# H1BR7.net
KiCad netlist of a schematic drawn in EAGLE
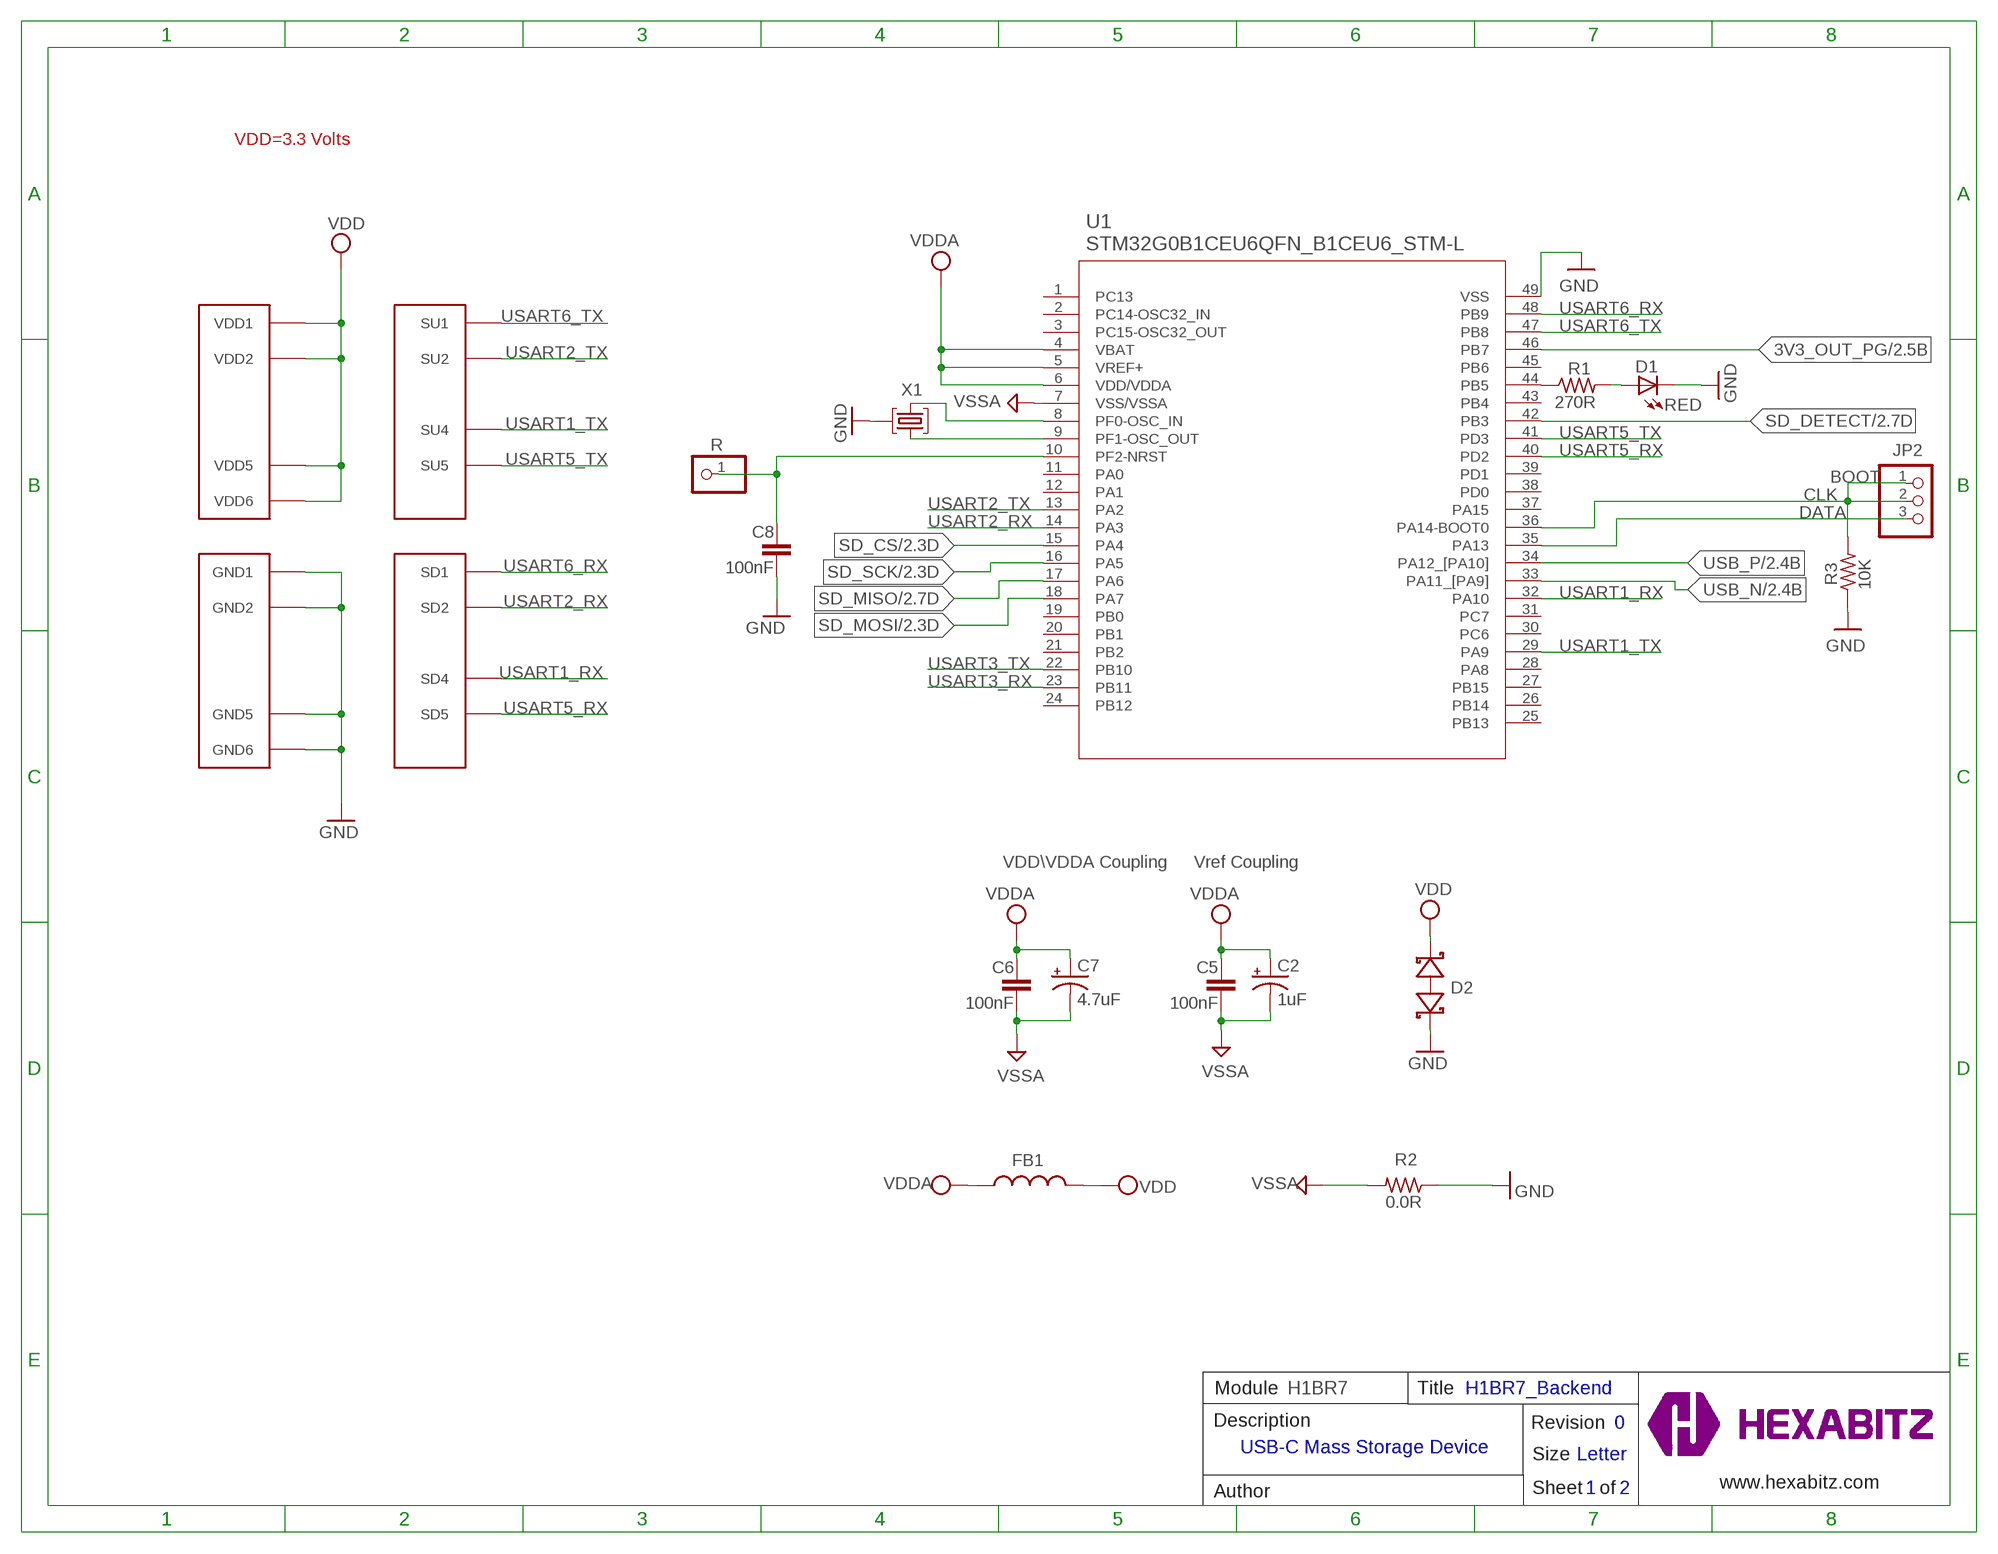
[diagram p0: schematic, sheet 1]
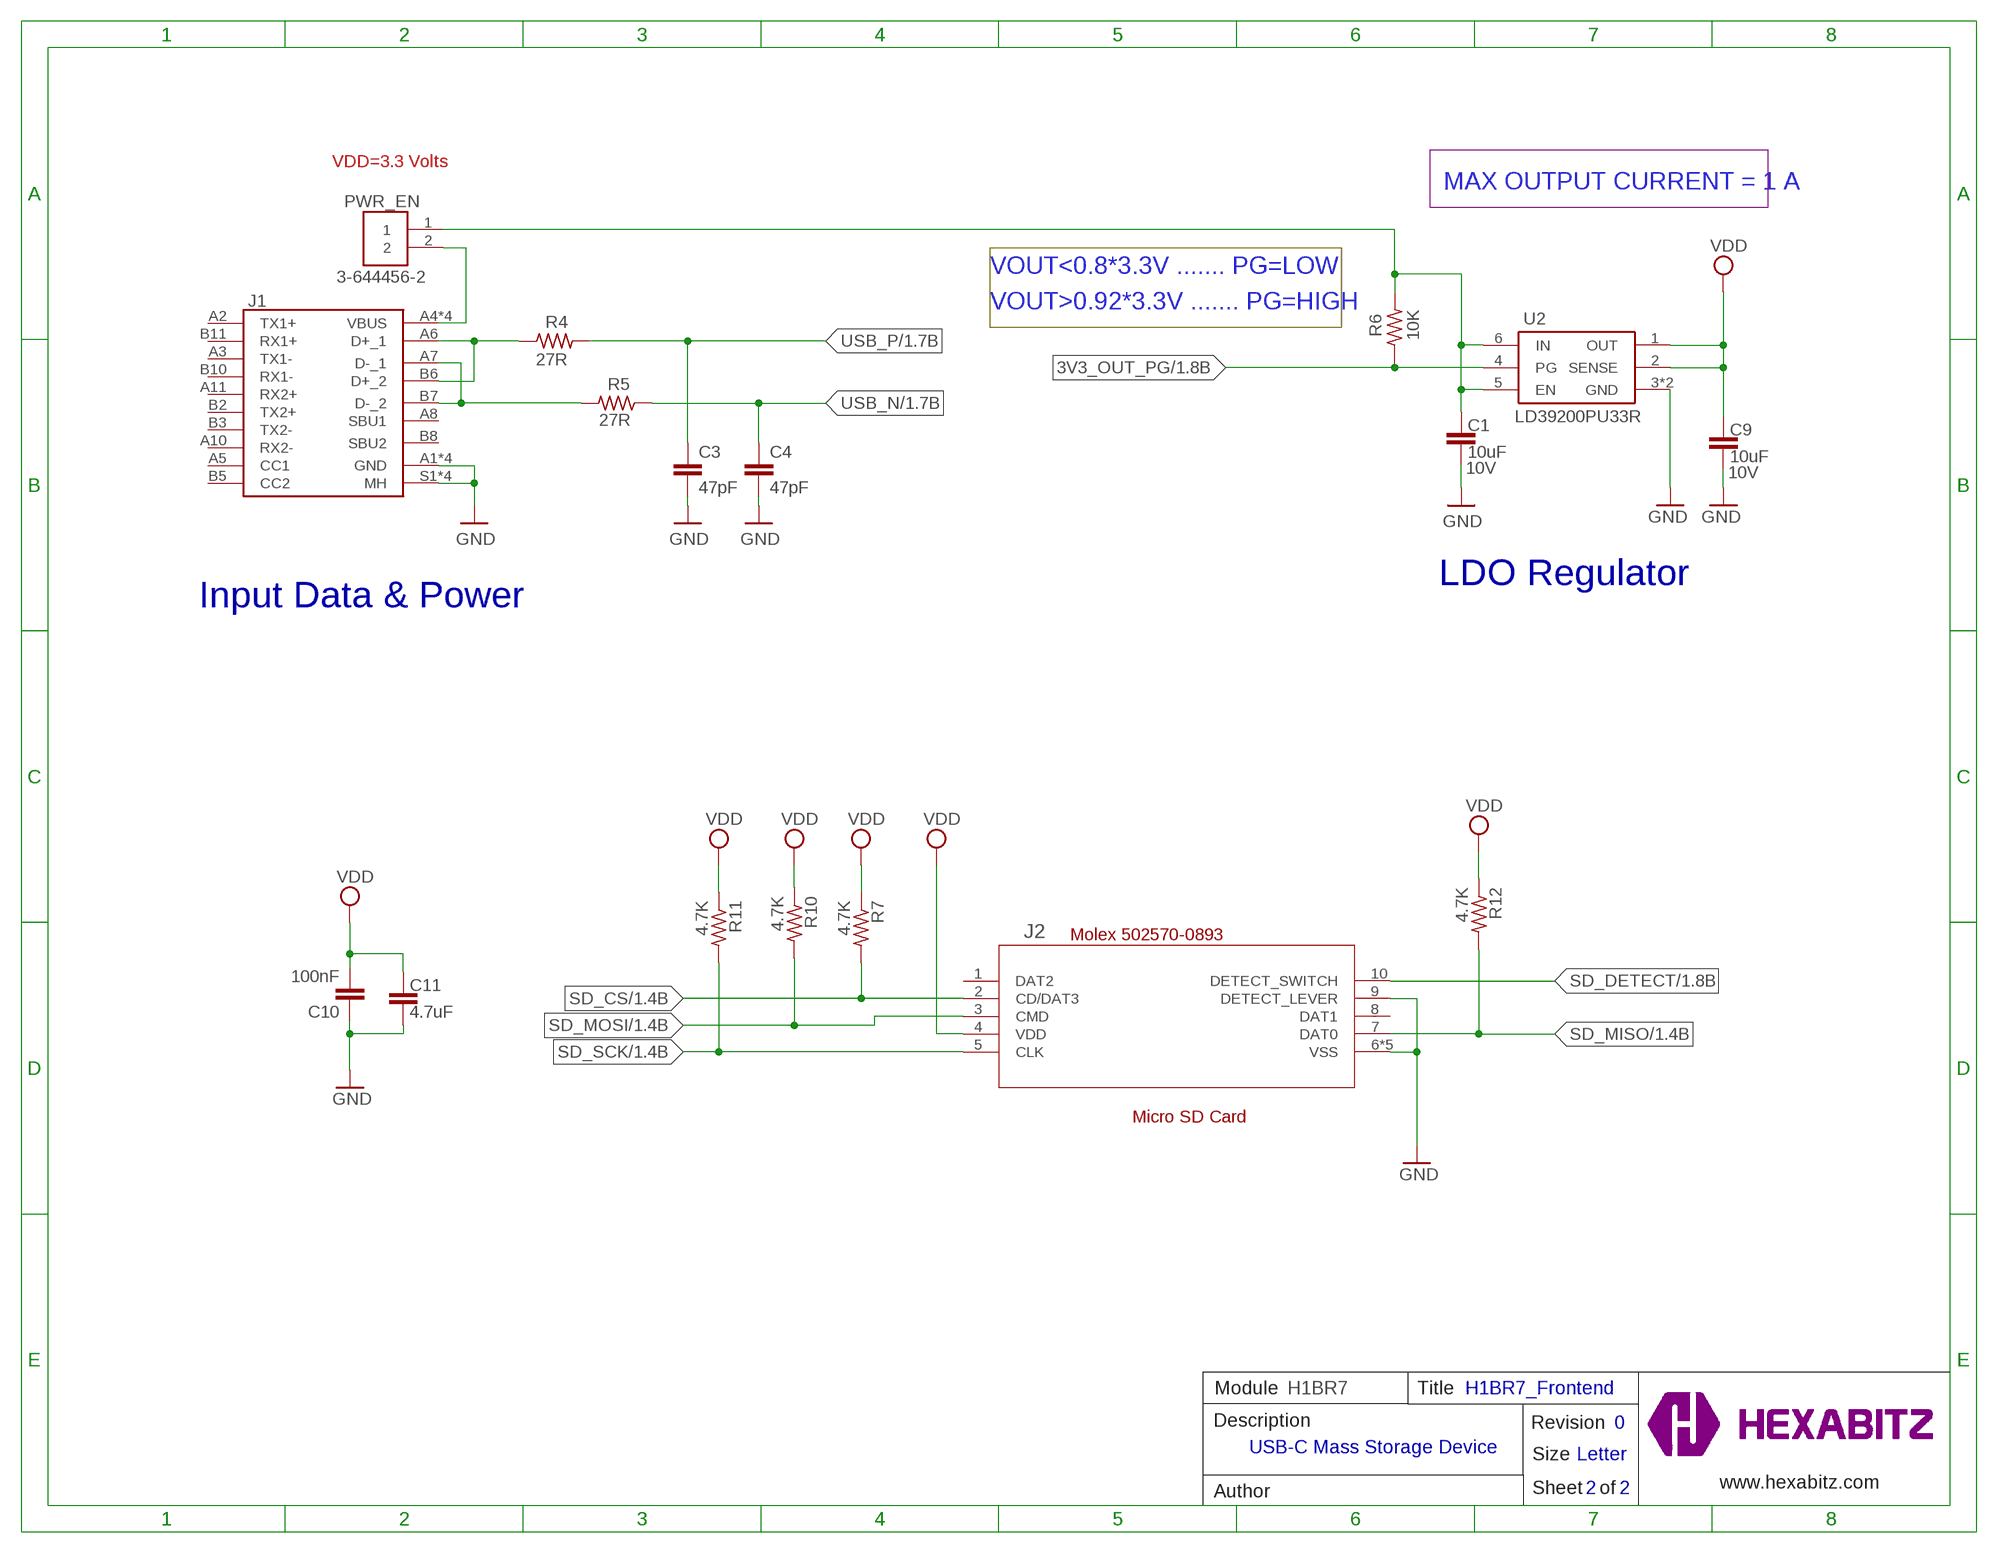
[diagram p1: schematic, sheet 2]

(export (version "E")
  (design (tool "Eeschema 10.0.6"))
  (components
    (comp (ref "C1")
      (value "10uF")
      (footprint "eagle-import:C-0805")
      (fields (field (name "MPN") "GRM187R61A226ME15") (field (name "VOLTAGE_RATING") "10V"))
      (libsource (lib "eagle-import") (part "C-0805"))
    )
    (comp (ref "C3")
      (value "47pF")
      (footprint "eagle-import:C-0603")
      (libsource (lib "eagle-import") (part "C-0603"))
    )
    (comp (ref "C4")
      (value "47pF")
      (footprint "eagle-import:C-0603")
      (libsource (lib "eagle-import") (part "C-0603"))
    )
    (comp (ref "C9")
      (value "10uF")
      (footprint "eagle-import:C-0805")
      (fields (field (name "MPN") "GRM187R61A226ME15") (field (name "VOLTAGE_RATING") "10V"))
      (libsource (lib "eagle-import") (part "C-0805"))
    )
    (comp (ref "C10")
      (value "100nF")
      (footprint "eagle-import:C-0603")
      (fields
        (field (name "CAPACITANCE") "100nF")
        (field (name "MFN") "AVX CORPORATION")
        (field (name "MPN") "'0603YC104K4T2A")
        (field (name "OCTOPART_URL") "'https://octopart.com/0603yc104k4t2a-avx+interconnect+%2F+elco-8120651")
        (field (name "TOLERANCE") "10%")
        (field (name "VOLTAGE_RATING") "16.0 V")
      )
      (libsource (lib "eagle-import") (part "C-0603"))
    )
    (comp (ref "C11")
      (value "4.7uF")
      (footprint "eagle-import:C-0805")
      (fields (field (name "MPN") "GRM187R61A226ME15") (field (name "VOLTAGE_RATING") "10V"))
      (libsource (lib "eagle-import") (part "C-0805"))
    )
    (comp (ref "J1")
      (value "12401610E4#2A12401610E42A")
      (footprint "eagle-import:AMPHENOL_12401610E4_2A")
      (libsource (lib "eagle-import") (part "12401610E4#2A12401610E42A"))
    )
    (comp (ref "J2")
      (value "5025700893502570-0893_MOL")
      (footprint "eagle-import:502570-0893_MOL")
      (fields
        (field (name "MANUFACTURER_PART_NUMBER") "5025700893")
        (field (name "COPYRIGHT") "Copyright (C) 2022 Ultra Librarian. All rights reserved.")
      )
      (libsource (lib "eagle-import") (part "5025700893502570-0893_MOL"))
    )
    (comp (ref "PWR_EN")
      (value "3-644456-2")
      (footprint "eagle-import:TE_3-644456-2")
      (fields (field (name "MF") "TE Connectivity") (field (name "MPN") "87224-1"))
      (libsource (lib "eagle-import") (part "3-644456-2"))
    )
    (comp (ref "R4")
      (value "27R")
      (footprint "eagle-import:R-0603")
      (fields (field (name "TOLERANCE") "1%"))
      (libsource (lib "eagle-import") (part "R-0603"))
    )
    (comp (ref "R5")
      (value "27R")
      (footprint "eagle-import:R-0603")
      (fields (field (name "TOLERANCE") "1%"))
      (libsource (lib "eagle-import") (part "R-0603"))
    )
    (comp (ref "R6")
      (value "10K")
      (footprint "eagle-import:R-0603")
      (fields (field (name "TOLERANCE") "1%"))
      (libsource (lib "eagle-import") (part "R-0603"))
    )
    (comp (ref "R7")
      (value "4.7K")
      (footprint "eagle-import:R-0603")
      (fields
        (field (name "MFN") "YAGED [VA]")
        (field (name "MPN") "RC0603JR-074K7L")
        (field (name "OCTOPART_URL") "'https://octopart.com/rc0603jr-074k7l-yageo-55458509?r=sp")
        (field (name "RESISTANCE") "4700 Ohm")
        (field (name "TOLERANCE") "5%")
      )
      (libsource (lib "eagle-import") (part "R-0603"))
    )
    (comp (ref "R10")
      (value "4.7K")
      (footprint "eagle-import:R-0603")
      (fields
        (field (name "MFN") "YAGED [VA]")
        (field (name "MPN") "RC0603JR-074K7L")
        (field (name "OCTOPART_URL") "'https://octopart.com/rc0603jr-074k7l-yageo-55458509?r=sp")
        (field (name "RESISTANCE") "4700 Ohm")
        (field (name "TOLERANCE") "5%")
      )
      (libsource (lib "eagle-import") (part "R-0603"))
    )
    (comp (ref "R11")
      (value "4.7K")
      (footprint "eagle-import:R-0603")
      (fields
        (field (name "MFN") "YAGED [VA]")
        (field (name "MPN") "RC0603JR-074K7L")
        (field (name "OCTOPART_URL") "'https://octopart.com/rc0603jr-074k7l-yageo-55458509?r=sp")
        (field (name "RESISTANCE") "4700 Ohm")
        (field (name "TOLERANCE") "5%")
      )
      (libsource (lib "eagle-import") (part "R-0603"))
    )
    (comp (ref "R12")
      (value "4.7K")
      (footprint "eagle-import:R-0603")
      (fields
        (field (name "MFN") "YAGED [VA]")
        (field (name "MPN") "RC0603JR-074K7L")
        (field (name "OCTOPART_URL") "'https://octopart.com/rc0603jr-074k7l-yageo-55458509?r=sp")
        (field (name "RESISTANCE") "4700 Ohm")
        (field (name "TOLERANCE") "5%")
      )
      (libsource (lib "eagle-import") (part "R-0603"))
    )
    (comp (ref "U2")
      (value "LD39200PU33R")
      (footprint "eagle-import:SON95P300X300X100-7N")
      (fields (field (name "MOUSER_PART_NUMBER") "511-LD39200PU33R"))
      (libsource (lib "eagle-import") (part "LD39200PU33R"))
    )
    (comp (ref "C2")
      (value "1uF")
      (footprint "eagle-import:C-0805-POL")
      (libsource (lib "eagle-import") (part "C-0805-POL"))
    )
    (comp (ref "C5")
      (value "100nF")
      (footprint "eagle-import:C-0603")
      (libsource (lib "eagle-import") (part "C-0603"))
    )
    (comp (ref "C6")
      (value "100nF")
      (footprint "eagle-import:C-0603")
      (libsource (lib "eagle-import") (part "C-0603"))
    )
    (comp (ref "C7")
      (value "4.7uF")
      (footprint "eagle-import:C-0805-POL")
      (libsource (lib "eagle-import") (part "C-0805-POL"))
    )
    (comp (ref "C8")
      (value "100nF")
      (footprint "eagle-import:C-0603")
      (libsource (lib "eagle-import") (part "C-0603"))
    )
    (comp (ref "D1")
      (value "RED")
      (footprint "eagle-import:VLMS1300-GS08")
      (fields
        (field (name "MPN") "VLMS1300-GS08")
        (field (name "MFN") "Vishay")
        (field (name "MPN_1") "VLMS1300-GS08")
        (field (name "OCTOPART_URL") "https://octopart.com/vlms1300-gs08-vishay-21709201?r=sp&s=_gcP4_q8T1SC6PJQPTQ9yA")
      )
      (libsource (lib "eagle-import") (part "VLMS1300-GS08"))
    )
    (comp (ref "D2")
      (value "BOURNS_CDSOD323-T03SCBOURNS_CDSOD323-T03SC_0_0")
      (footprint "eagle-import:BOURNS_CDSOD323-T03SC_0")
      (fields (field (name "MPN") "CDSOD323-T03SC"))
      (libsource (lib "eagle-import") (part "BOURNS_CDSOD323-T03SCBOURNS_CDSOD323-T03SC_0_0"))
    )
    (comp (ref "FB1")
      (value "FB-TDK_MMZ1608Y300B")
      (footprint "eagle-import:FB-TDK_MMZ1608Y300B")
      (fields
        (field (name "MFN") "TDK ")
        (field (name "MPN") "MMZ1608Y300B")
        (field (name "OCTOPART_URL") "https://octopart.com/mmz1608y300b-tdk-368280?r=sp&s=cd9_2ZEqQ9q9UNBuQgHAiA")
      )
      (libsource (lib "eagle-import") (part "FB-TDK_MMZ1608Y300B"))
    )
    (comp (ref "JP2")
      (value "PINHD-1X3")
      (footprint "eagle-import:1X03")
      (libsource (lib "eagle-import") (part "PINHD-1X3"))
    )
    (comp (ref "P1")
      (value "HEXABIT_HEXABIT_?_NO_P3_P6_P9_P10")
      (footprint "eagle-import:HEXABIT___NO_P3_P6_P9_P10")
      (libsource (lib "eagle-import") (part "HEXABIT_?_NO_P3_P6_P9_P10HEXABIT_?_NO_P3_P6_P9_P10"))
    )
    (comp (ref "R")
      (value "R")
      (footprint "eagle-import:1X01")
      (fields (field (name "MPN") "87227-1"))
      (libsource (lib "eagle-import") (part "PINHD-1X1"))
    )
    (comp (ref "R1")
      (value "270R")
      (footprint "eagle-import:R-0603")
      (libsource (lib "eagle-import") (part "R-0603"))
    )
    (comp (ref "R2")
      (value "0.0R")
      (footprint "eagle-import:R-0603")
      (fields
        (field (name "MFN") "Yageo")
        (field (name "MPN") "RC0603JR-070RL")
        (field (name "OCTOPART_URL") "https://octopart.com/rc0603jr-070rl-yageo-1241539?r=sp&s=X2NteqRjRNWrnx42Y0aliA")
        (field (name "RESISTANCE") "0.0 Ohm")
      )
      (libsource (lib "eagle-import") (part "R-0603"))
    )
    (comp (ref "R3")
      (value "10K")
      (footprint "eagle-import:R-0603")
      (libsource (lib "eagle-import") (part "R-0603"))
    )
    (comp (ref "TRIMBLE-LOGO1")
      (value "HEXA-LOGO")
      (footprint "eagle-import:HEXA-LOGO")
      (libsource (lib "eagle-import") (part "HEXA-LOGO"))
    )
    (comp (ref "U1")
      (value "STM32G0B1CEU6QFN_B1CEU6_STM-L")
      (footprint "eagle-import:QFN_B1CEU6_STM-L")
      (fields
        (field (name "MANUFACTURER_PART_NUMBER") "STM32G0B1CEU6")
        (field (name "COPYRIGHT") "Copyright (C) 2021 Ultra Librarian. All rights reserved.")
      )
      (libsource (lib "eagle-import") (part "STM32G0B1CEU6QFN_B1CEU6_STM-L"))
    )
    (comp (ref "X1")
      (value "XTALL_CSTCE8M00G52")
      (footprint "eagle-import:XTALL_CSTCE8M00G52")
      (fields (field (name "MPN") "CSTCE8M00G52Z-R0"))
      (libsource (lib "eagle-import") (part "XTALL_CSTCE8M00G52"))
    )
  )
  (nets
    (net (code "1") (name "3V3_OUT_PG") (class "Default")
      (node (ref "R6") (pin "1") (pinfunction "1_1") (pintype "passive"))
      (node (ref "U1") (pin "46") (pinfunction "PB7_46") (pintype "bidirectional"))
      (node (ref "U2") (pin "4") (pinfunction "PG_4") (pintype "bidirectional"))
    )
    (net (code "2") (name "CLK") (class "Default")
      (node (ref "JP2") (pin "1") (pinfunction "1_1") (pintype "passive"))
      (node (ref "JP2") (pin "2") (pinfunction "2_2") (pintype "passive"))
      (node (ref "R3") (pin "2") (pinfunction "2_2") (pintype "passive"))
      (node (ref "U1") (pin "36") (pinfunction "PA14-BOOT0_36") (pintype "bidirectional"))
    )
    (net (code "3") (name "DATA") (class "Default")
      (node (ref "JP2") (pin "3") (pinfunction "3_3") (pintype "passive"))
      (node (ref "U1") (pin "35") (pinfunction "PA13_35") (pintype "bidirectional"))
    )
    (net (code "4") (name "GND") (class "Default")
      (node (ref "C1") (pin "1") (pinfunction "1_1") (pintype "passive"))
      (node (ref "C10") (pin "1") (pinfunction "1_1") (pintype "passive"))
      (node (ref "C11") (pin "1") (pinfunction "1_1") (pintype "passive"))
      (node (ref "C3") (pin "2") (pinfunction "2_2") (pintype "passive"))
      (node (ref "C4") (pin "2") (pinfunction "2_2") (pintype "passive"))
      (node (ref "C8") (pin "2") (pinfunction "2_2") (pintype "passive"))
      (node (ref "C9") (pin "1") (pinfunction "1_1") (pintype "passive"))
      (node (ref "D1") (pin "C") (pinfunction "C_C") (pintype "passive"))
      (node (ref "D2") (pin "1") (pinfunction "A_1") (pintype "passive"))
      (node (ref "J1") (pin "A1") (pinfunction "GND_A1") (pintype "bidirectional"))
      (node (ref "J1") (pin "A12") (pinfunction "GND_A12") (pintype "bidirectional"))
      (node (ref "J1") (pin "B1") (pinfunction "GND_B1") (pintype "bidirectional"))
      (node (ref "J1") (pin "B12") (pinfunction "GND_B12") (pintype "bidirectional"))
      (node (ref "J1") (pin "S1") (pinfunction "MH_S1") (pintype "bidirectional"))
      (node (ref "J1") (pin "S2") (pinfunction "MH_S2") (pintype "bidirectional"))
      (node (ref "J1") (pin "S3") (pinfunction "MH_S3") (pintype "bidirectional"))
      (node (ref "J1") (pin "S4") (pinfunction "MH_S4") (pintype "bidirectional"))
      (node (ref "J2") (pin "11") (pinfunction "VSS_11") (pintype "passive"))
      (node (ref "J2") (pin "12") (pinfunction "VSS_12") (pintype "passive"))
      (node (ref "J2") (pin "13") (pinfunction "VSS_13") (pintype "passive"))
      (node (ref "J2") (pin "14") (pinfunction "VSS_14") (pintype "passive"))
      (node (ref "J2") (pin "6") (pinfunction "VSS_6") (pintype "passive"))
      (node (ref "J2") (pin "9") (pinfunction "DETECT_LEVER_9") (pintype "passive"))
      (node (ref "P1") (pin "PAD_PD11") (pinfunction "GND5_PAD_PD11") (pintype "power_in"))
      (node (ref "P1") (pin "PAD_PD12") (pinfunction "GND6_PAD_PD12") (pintype "power_in"))
      (node (ref "P1") (pin "PAD_PD7") (pinfunction "GND1_PAD_PD7") (pintype "power_in"))
      (node (ref "P1") (pin "PAD_PD8") (pinfunction "GND2_PAD_PD8") (pintype "power_in"))
      (node (ref "R2") (pin "1") (pinfunction "1_1") (pintype "passive"))
      (node (ref "R3") (pin "1") (pinfunction "1_1") (pintype "passive"))
      (node (ref "U1") (pin "49") (pinfunction "VSS_49") (pintype "passive"))
      (node (ref "U2") (pin "3") (pinfunction "GND_3") (pintype "bidirectional"))
      (node (ref "U2") (pin "7") (pinfunction "GND_7") (pintype "bidirectional"))
      (node (ref "X1") (pin "P$2") (pinfunction "2_P$2") (pintype "passive"))
    )
    (net (code "5") (name "Net-(D1-PadA)") (class "Default")
      (node (ref "D1") (pin "A") (pinfunction "A_A") (pintype "passive"))
      (node (ref "R1") (pin "2") (pinfunction "2_2") (pintype "passive"))
    )
    (net (code "6") (name "Net-(J1-D+_1)") (class "Default")
      (node (ref "J1") (pin "A6") (pinfunction "D+_1_A6") (pintype "bidirectional"))
      (node (ref "J1") (pin "B6") (pinfunction "D+_2_B6") (pintype "bidirectional"))
      (node (ref "R4") (pin "1") (pinfunction "1_1") (pintype "passive"))
    )
    (net (code "7") (name "Net-(J1-D-_1)") (class "Default")
      (node (ref "J1") (pin "A7") (pinfunction "D-_1_A7") (pintype "bidirectional"))
      (node (ref "J1") (pin "B7") (pinfunction "D-_2_B7") (pintype "bidirectional"))
      (node (ref "R5") (pin "2") (pinfunction "2_2") (pintype "passive"))
    )
    (net (code "8") (name "Net-(J1-VBUS-PadA4)") (class "Default")
      (node (ref "J1") (pin "A4") (pinfunction "VBUS_A4") (pintype "bidirectional"))
      (node (ref "J1") (pin "A9") (pinfunction "VBUS_A9") (pintype "bidirectional"))
      (node (ref "J1") (pin "B4") (pinfunction "VBUS_B4") (pintype "bidirectional"))
      (node (ref "J1") (pin "B9") (pinfunction "VBUS_B9") (pintype "bidirectional"))
      (node (ref "PWR_EN") (pin "2") (pinfunction "2_2") (pintype "passive"))
    )
    (net (code "9") (name "Net-(U1-PB5)") (class "Default")
      (node (ref "R1") (pin "1") (pinfunction "1_1") (pintype "passive"))
      (node (ref "U1") (pin "44") (pinfunction "PB5_44") (pintype "bidirectional"))
    )
    (net (code "10") (name "Net-(U1-PF0-OSC_IN)") (class "Default")
      (node (ref "U1") (pin "8") (pinfunction "PF0-OSC_IN_8") (pintype "bidirectional"))
      (node (ref "X1") (pin "P$3") (pinfunction "3_P$3") (pintype "passive"))
    )
    (net (code "11") (name "Net-(U1-PF1-OSC_OUT)") (class "Default")
      (node (ref "U1") (pin "9") (pinfunction "PF1-OSC_OUT_9") (pintype "output"))
      (node (ref "X1") (pin "P$1") (pinfunction "1_P$1") (pintype "passive"))
    )
    (net (code "12") (name "Net-(U1-PF2-NRST)") (class "Default")
      (node (ref "C8") (pin "1") (pinfunction "1_1") (pintype "passive"))
      (node (ref "R") (pin "1") (pinfunction "1_1") (pintype "passive"))
      (node (ref "U1") (pin "10") (pinfunction "PF2-NRST_10") (pintype "bidirectional"))
    )
    (net (code "13") (name "Net-(U2-EN)") (class "Default")
      (node (ref "C1") (pin "2") (pinfunction "2_2") (pintype "passive"))
      (node (ref "PWR_EN") (pin "1") (pinfunction "1_1") (pintype "passive"))
      (node (ref "R6") (pin "2") (pinfunction "2_2") (pintype "passive"))
      (node (ref "U2") (pin "5") (pinfunction "EN_5") (pintype "bidirectional"))
      (node (ref "U2") (pin "6") (pinfunction "IN_6") (pintype "bidirectional"))
    )
    (net (code "14") (name "SD_CS") (class "Default")
      (node (ref "J2") (pin "2") (pinfunction "CD/DAT3_2") (pintype "passive"))
      (node (ref "R7") (pin "2") (pinfunction "2_2") (pintype "passive"))
      (node (ref "U1") (pin "15") (pinfunction "PA4_15") (pintype "bidirectional"))
    )
    (net (code "15") (name "SD_DETECT") (class "Default")
      (node (ref "J2") (pin "10") (pinfunction "DETECT_SWITCH_10") (pintype "passive"))
      (node (ref "U1") (pin "42") (pinfunction "PB3_42") (pintype "bidirectional"))
    )
    (net (code "16") (name "SD_MISO") (class "Default")
      (node (ref "J2") (pin "7") (pinfunction "DAT0_7") (pintype "bidirectional"))
      (node (ref "R12") (pin "2") (pinfunction "2_2") (pintype "passive"))
      (node (ref "U1") (pin "17") (pinfunction "PA6_17") (pintype "bidirectional"))
    )
    (net (code "17") (name "SD_MOSI") (class "Default")
      (node (ref "J2") (pin "3") (pinfunction "CMD_3") (pintype "passive"))
      (node (ref "R10") (pin "2") (pinfunction "2_2") (pintype "passive"))
      (node (ref "U1") (pin "18") (pinfunction "PA7_18") (pintype "bidirectional"))
    )
    (net (code "18") (name "SD_SCK") (class "Default")
      (node (ref "J2") (pin "5") (pinfunction "CLK_5") (pintype "passive"))
      (node (ref "R11") (pin "2") (pinfunction "2_2") (pintype "passive"))
      (node (ref "U1") (pin "16") (pinfunction "PA5_16") (pintype "bidirectional"))
    )
    (net (code "19") (name "USART1_RX") (class "Default")
      (node (ref "P1") (pin "PAD_PD4") (pinfunction "SD4_PAD_PD4") (pintype "bidirectional"))
      (node (ref "U1") (pin "32") (pinfunction "PA10_32") (pintype "bidirectional"))
    )
    (net (code "20") (name "USART1_TX") (class "Default")
      (node (ref "P1") (pin "PAD_PU4") (pinfunction "SU4_PAD_PU4") (pintype "bidirectional"))
      (node (ref "U1") (pin "29") (pinfunction "PA9_29") (pintype "bidirectional"))
    )
    (net (code "21") (name "USART2_RX") (class "Default")
      (node (ref "P1") (pin "PAD_PD2") (pinfunction "SD2_PAD_PD2") (pintype "bidirectional"))
      (node (ref "U1") (pin "14") (pinfunction "PA3_14") (pintype "bidirectional"))
    )
    (net (code "22") (name "USART2_TX") (class "Default")
      (node (ref "P1") (pin "PAD_PU2") (pinfunction "SU2_PAD_PU2") (pintype "bidirectional"))
      (node (ref "U1") (pin "13") (pinfunction "PA2_13") (pintype "bidirectional"))
    )
    (net (code "23") (name "USART3_RX") (class "Default")
      (node (ref "U1") (pin "23") (pinfunction "PB11_23") (pintype "bidirectional"))
    )
    (net (code "24") (name "USART3_TX") (class "Default")
      (node (ref "U1") (pin "22") (pinfunction "PB10_22") (pintype "bidirectional"))
    )
    (net (code "25") (name "USART5_RX") (class "Default")
      (node (ref "P1") (pin "PAD_PD5") (pinfunction "SD5_PAD_PD5") (pintype "bidirectional"))
      (node (ref "U1") (pin "40") (pinfunction "PD2_40") (pintype "bidirectional"))
    )
    (net (code "26") (name "USART5_TX") (class "Default")
      (node (ref "P1") (pin "PAD_PU5") (pinfunction "SU5_PAD_PU5") (pintype "bidirectional"))
      (node (ref "U1") (pin "41") (pinfunction "PD3_41") (pintype "bidirectional"))
    )
    (net (code "27") (name "USART6_RX") (class "Default")
      (node (ref "P1") (pin "PAD_PD1") (pinfunction "SD1_PAD_PD1") (pintype "bidirectional"))
      (node (ref "U1") (pin "48") (pinfunction "PB9_48") (pintype "bidirectional"))
    )
    (net (code "28") (name "USART6_TX") (class "Default")
      (node (ref "P1") (pin "PAD_PU1") (pinfunction "SU1_PAD_PU1") (pintype "bidirectional"))
      (node (ref "U1") (pin "47") (pinfunction "PB8_47") (pintype "bidirectional"))
    )
    (net (code "29") (name "USB_N") (class "Default")
      (node (ref "C4") (pin "1") (pinfunction "1_1") (pintype "passive"))
      (node (ref "R5") (pin "1") (pinfunction "1_1") (pintype "passive"))
      (node (ref "U1") (pin "33") (pinfunction "PA11_[PA9]_33") (pintype "bidirectional"))
    )
    (net (code "30") (name "USB_P") (class "Default")
      (node (ref "C3") (pin "1") (pinfunction "1_1") (pintype "passive"))
      (node (ref "R4") (pin "2") (pinfunction "2_2") (pintype "passive"))
      (node (ref "U1") (pin "34") (pinfunction "PA12_[PA10]_34") (pintype "bidirectional"))
    )
    (net (code "31") (name "VDD") (class "Default")
      (node (ref "C10") (pin "2") (pinfunction "2_2") (pintype "passive"))
      (node (ref "C11") (pin "2") (pinfunction "2_2") (pintype "passive"))
      (node (ref "C9") (pin "2") (pinfunction "2_2") (pintype "passive"))
      (node (ref "D2") (pin "2") (pinfunction "C_2") (pintype "passive"))
      (node (ref "FB1") (pin "2") (pinfunction "2_2") (pintype "passive"))
      (node (ref "J2") (pin "4") (pinfunction "VDD_4") (pintype "power_in"))
      (node (ref "P1") (pin "PAD_PU11") (pinfunction "VDD5_PAD_PU11") (pintype "power_in"))
      (node (ref "P1") (pin "PAD_PU12") (pinfunction "VDD6_PAD_PU12") (pintype "power_in"))
      (node (ref "P1") (pin "PAD_PU7") (pinfunction "VDD1_PAD_PU7") (pintype "power_in"))
      (node (ref "P1") (pin "PAD_PU8") (pinfunction "VDD2_PAD_PU8") (pintype "power_in"))
      (node (ref "R10") (pin "1") (pinfunction "1_1") (pintype "passive"))
      (node (ref "R11") (pin "1") (pinfunction "1_1") (pintype "passive"))
      (node (ref "R12") (pin "1") (pinfunction "1_1") (pintype "passive"))
      (node (ref "R7") (pin "1") (pinfunction "1_1") (pintype "passive"))
      (node (ref "U2") (pin "1") (pinfunction "OUT_1") (pintype "bidirectional"))
      (node (ref "U2") (pin "2") (pinfunction "SENSE_2") (pintype "bidirectional"))
    )
    (net (code "32") (name "VDDA") (class "Default")
      (node (ref "C2") (pin "1") (pinfunction "+_1") (pintype "passive"))
      (node (ref "C5") (pin "1") (pinfunction "1_1") (pintype "passive"))
      (node (ref "C6") (pin "1") (pinfunction "1_1") (pintype "passive"))
      (node (ref "C7") (pin "1") (pinfunction "+_1") (pintype "passive"))
      (node (ref "FB1") (pin "1") (pinfunction "1_1") (pintype "passive"))
      (node (ref "U1") (pin "4") (pinfunction "VBAT_4") (pintype "passive"))
      (node (ref "U1") (pin "5") (pinfunction "VREF+_5") (pintype "power_in"))
      (node (ref "U1") (pin "6") (pinfunction "VDD/VDDA_6") (pintype "power_in"))
    )
    (net (code "33") (name "VSSA") (class "Default")
      (node (ref "C2") (pin "2") (pinfunction "-_2") (pintype "passive"))
      (node (ref "C5") (pin "2") (pinfunction "2_2") (pintype "passive"))
      (node (ref "C6") (pin "2") (pinfunction "2_2") (pintype "passive"))
      (node (ref "C7") (pin "2") (pinfunction "-_2") (pintype "passive"))
      (node (ref "R2") (pin "2") (pinfunction "2_2") (pintype "passive"))
      (node (ref "U1") (pin "7") (pinfunction "VSS/VSSA_7") (pintype "passive"))
    )
    (net (code "34") (name "unconnected-(J1-CC1-PadA5)") (class "Default")
      (node (ref "J1") (pin "A5") (pinfunction "CC1_A5") (pintype "bidirectional"))
    )
    (net (code "35") (name "unconnected-(J1-CC2-PadB5)") (class "Default")
      (node (ref "J1") (pin "B5") (pinfunction "CC2_B5") (pintype "bidirectional"))
    )
    (net (code "36") (name "unconnected-(J1-RX1+-PadB11)") (class "Default")
      (node (ref "J1") (pin "B11") (pinfunction "RX1+_B11") (pintype "bidirectional"))
    )
    (net (code "37") (name "unconnected-(J1-RX1--PadB10)") (class "Default")
      (node (ref "J1") (pin "B10") (pinfunction "RX1-_B10") (pintype "bidirectional"))
    )
    (net (code "38") (name "unconnected-(J1-RX2+-PadA11)") (class "Default")
      (node (ref "J1") (pin "A11") (pinfunction "RX2+_A11") (pintype "bidirectional"))
    )
    (net (code "39") (name "unconnected-(J1-RX2--PadA10)") (class "Default")
      (node (ref "J1") (pin "A10") (pinfunction "RX2-_A10") (pintype "bidirectional"))
    )
    (net (code "40") (name "unconnected-(J1-SBU1-PadA8)") (class "Default")
      (node (ref "J1") (pin "A8") (pinfunction "SBU1_A8") (pintype "bidirectional"))
    )
    (net (code "41") (name "unconnected-(J1-SBU2-PadB8)") (class "Default")
      (node (ref "J1") (pin "B8") (pinfunction "SBU2_B8") (pintype "bidirectional"))
    )
    (net (code "42") (name "unconnected-(J1-TX1+-PadA2)") (class "Default")
      (node (ref "J1") (pin "A2") (pinfunction "TX1+_A2") (pintype "bidirectional"))
    )
    (net (code "43") (name "unconnected-(J1-TX1--PadA3)") (class "Default")
      (node (ref "J1") (pin "A3") (pinfunction "TX1-_A3") (pintype "bidirectional"))
    )
    (net (code "44") (name "unconnected-(J1-TX2+-PadB2)") (class "Default")
      (node (ref "J1") (pin "B2") (pinfunction "TX2+_B2") (pintype "bidirectional"))
    )
    (net (code "45") (name "unconnected-(J1-TX2--PadB3)") (class "Default")
      (node (ref "J1") (pin "B3") (pinfunction "TX2-_B3") (pintype "bidirectional"))
    )
    (net (code "46") (name "unconnected-(J2-DAT1-Pad8)") (class "Default")
      (node (ref "J2") (pin "8") (pinfunction "DAT1_8") (pintype "bidirectional"))
    )
    (net (code "47") (name "unconnected-(J2-DAT2-Pad1)") (class "Default")
      (node (ref "J2") (pin "1") (pinfunction "DAT2_1") (pintype "bidirectional"))
    )
    (net (code "48") (name "unconnected-(U1-PA0-Pad11)") (class "Default")
      (node (ref "U1") (pin "11") (pinfunction "PA0_11") (pintype "bidirectional"))
    )
    (net (code "49") (name "unconnected-(U1-PA1-Pad12)") (class "Default")
      (node (ref "U1") (pin "12") (pinfunction "PA1_12") (pintype "bidirectional"))
    )
    (net (code "50") (name "unconnected-(U1-PA8-Pad28)") (class "Default")
      (node (ref "U1") (pin "28") (pinfunction "PA8_28") (pintype "bidirectional"))
    )
    (net (code "51") (name "unconnected-(U1-PA15-Pad37)") (class "Default")
      (node (ref "U1") (pin "37") (pinfunction "PA15_37") (pintype "bidirectional"))
    )
    (net (code "52") (name "unconnected-(U1-PB0-Pad19)") (class "Default")
      (node (ref "U1") (pin "19") (pinfunction "PB0_19") (pintype "bidirectional"))
    )
    (net (code "53") (name "unconnected-(U1-PB1-Pad20)") (class "Default")
      (node (ref "U1") (pin "20") (pinfunction "PB1_20") (pintype "bidirectional"))
    )
    (net (code "54") (name "unconnected-(U1-PB2-Pad21)") (class "Default")
      (node (ref "U1") (pin "21") (pinfunction "PB2_21") (pintype "bidirectional"))
    )
    (net (code "55") (name "unconnected-(U1-PB4-Pad43)") (class "Default")
      (node (ref "U1") (pin "43") (pinfunction "PB4_43") (pintype "bidirectional"))
    )
    (net (code "56") (name "unconnected-(U1-PB6-Pad45)") (class "Default")
      (node (ref "U1") (pin "45") (pinfunction "PB6_45") (pintype "bidirectional"))
    )
    (net (code "57") (name "unconnected-(U1-PB12-Pad24)") (class "Default")
      (node (ref "U1") (pin "24") (pinfunction "PB12_24") (pintype "bidirectional"))
    )
    (net (code "58") (name "unconnected-(U1-PB13-Pad25)") (class "Default")
      (node (ref "U1") (pin "25") (pinfunction "PB13_25") (pintype "bidirectional"))
    )
    (net (code "59") (name "unconnected-(U1-PB14-Pad26)") (class "Default")
      (node (ref "U1") (pin "26") (pinfunction "PB14_26") (pintype "bidirectional"))
    )
    (net (code "60") (name "unconnected-(U1-PB15-Pad27)") (class "Default")
      (node (ref "U1") (pin "27") (pinfunction "PB15_27") (pintype "bidirectional"))
    )
    (net (code "61") (name "unconnected-(U1-PC6-Pad30)") (class "Default")
      (node (ref "U1") (pin "30") (pinfunction "PC6_30") (pintype "bidirectional"))
    )
    (net (code "62") (name "unconnected-(U1-PC7-Pad31)") (class "Default")
      (node (ref "U1") (pin "31") (pinfunction "PC7_31") (pintype "bidirectional"))
    )
    (net (code "63") (name "unconnected-(U1-PC13-Pad1)") (class "Default")
      (node (ref "U1") (pin "1") (pinfunction "PC13_1") (pintype "bidirectional"))
    )
    (net (code "64") (name "unconnected-(U1-PC14-OSC32_IN-Pad2)") (class "Default")
      (node (ref "U1") (pin "2") (pinfunction "PC14-OSC32_IN_2") (pintype "bidirectional"))
    )
    (net (code "65") (name "unconnected-(U1-PC15-OSC32_OUT-Pad3)") (class "Default")
      (node (ref "U1") (pin "3") (pinfunction "PC15-OSC32_OUT_3") (pintype "output"))
    )
    (net (code "66") (name "unconnected-(U1-PD0-Pad38)") (class "Default")
      (node (ref "U1") (pin "38") (pinfunction "PD0_38") (pintype "bidirectional"))
    )
    (net (code "67") (name "unconnected-(U1-PD1-Pad39)") (class "Default")
      (node (ref "U1") (pin "39") (pinfunction "PD1_39") (pintype "bidirectional"))
    )
  )
)
